# Moty_Light.net
KiCad netlist of a schematic drawn in EAGLE
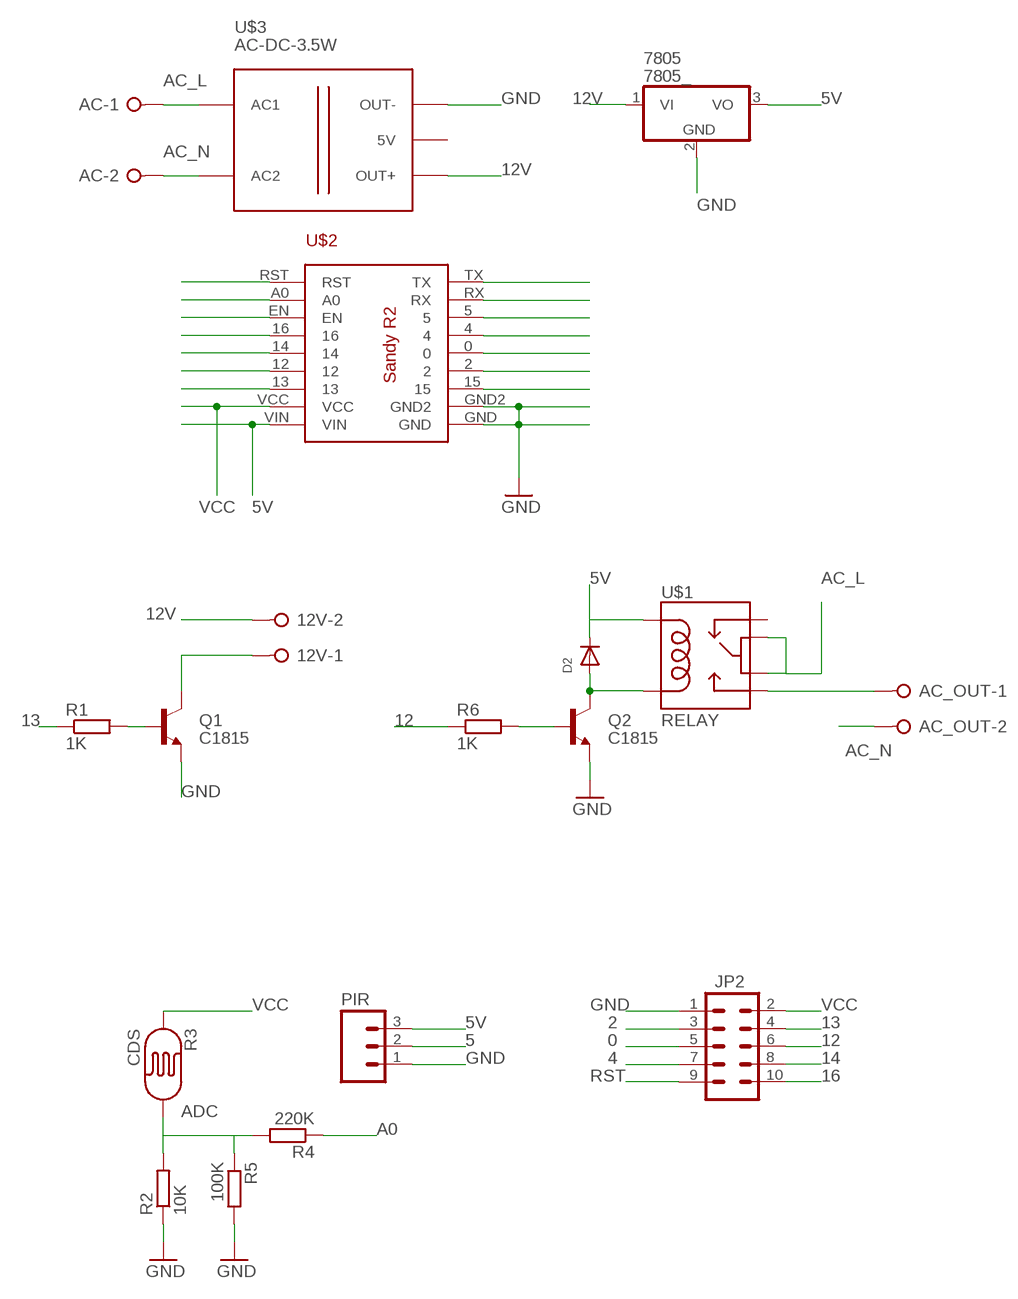
[diagram p0: schematic, sheet 1]

(export (version "E")
  (design (tool "Eeschema 10.0.6"))
  (components
    (comp (ref "12V")
      (value "W237-02P")
      (footprint "eagle-import:W237-132")
      (libsource (lib "eagle-import") (part "W237-02P"))
    )
    (comp (ref "7805")
      (value "7805_")
      (footprint "eagle-import:TO220V")
      (libsource (lib "eagle-import") (part "78TV05"))
    )
    (comp (ref "AC")
      (value "W237-02P")
      (footprint "eagle-import:W237-132")
      (libsource (lib "eagle-import") (part "W237-02P"))
    )
    (comp (ref "AC_OUT")
      (value "W237-02P")
      (footprint "eagle-import:W237-132")
      (libsource (lib "eagle-import") (part "W237-02P"))
    )
    (comp (ref "D2")
      (value "DIODESMA")
      (footprint "eagle-import:SMADIODE")
      (libsource (lib "eagle-import") (part "DIODESMA"))
    )
    (comp (ref "JP2")
      (value "M05X2PTH")
      (footprint "eagle-import:AVR_ICSP")
      (libsource (lib "eagle-import") (part "M05X2PTH"))
    )
    (comp (ref "PIR")
      (value "M03PTH")
      (footprint "eagle-import:1X03")
      (libsource (lib "eagle-import") (part "M03PTH"))
    )
    (comp (ref "Q1")
      (value "C1815")
      (footprint "eagle-import:SOT23-3")
      (libsource (lib "eagle-import") (part "TRANSISTOR_NPNMMBT2222A"))
    )
    (comp (ref "Q2")
      (value "C1815")
      (footprint "eagle-import:SOT23-3")
      (libsource (lib "eagle-import") (part "TRANSISTOR_NPNMMBT2222A"))
    )
    (comp (ref "R1")
      (value "1K")
      (footprint "eagle-import:R0805")
      (libsource (lib "eagle-import") (part "R-EU_R0805"))
    )
    (comp (ref "R2")
      (value "10K")
      (footprint "eagle-import:R0805")
      (libsource (lib "eagle-import") (part "R-EU_R0805"))
    )
    (comp (ref "R3")
      (value "CDS")
      (footprint "eagle-import:PHOTOCELL_THIN")
      (libsource (lib "eagle-import") (part "PHOTOCELL"))
    )
    (comp (ref "R4")
      (value "220K")
      (footprint "eagle-import:R0805")
      (libsource (lib "eagle-import") (part "R-EU_R0805"))
    )
    (comp (ref "R5")
      (value "100K")
      (footprint "eagle-import:R0805")
      (libsource (lib "eagle-import") (part "R-EU_R0805"))
    )
    (comp (ref "R6")
      (value "1K")
      (footprint "eagle-import:R0805")
      (libsource (lib "eagle-import") (part "R-EU_R0805"))
    )
    (comp (ref "U$1")
      (value "RELAY")
      (footprint "eagle-import:MINIATURE_RELAY_JRC_21F")
      (libsource (lib "eagle-import") (part "MINIATURE_RELAY_JRC_21F"))
    )
    (comp (ref "U$2")
      (value "MINI-ESP")
      (footprint "eagle-import:MINI-ESP")
      (libsource (lib "eagle-import") (part "MINI-ESP"))
    )
    (comp (ref "U$3")
      (value "AC-DC-3.5W")
      (footprint "eagle-import:AC-DC-3.5W")
      (libsource (lib "eagle-import") (part "AC-DC-3.5W"))
    )
  )
  (nets
    (net (code "1") (name "/0") (class "Default")
      (node (ref "JP2") (pin "5") (pinfunction "5_5") (pintype "passive"))
      (node (ref "U$2") (pin "0") (pinfunction "0_0") (pintype "bidirectional"))
    )
    (net (code "2") (name "/2") (class "Default")
      (node (ref "JP2") (pin "3") (pinfunction "3_3") (pintype "passive"))
      (node (ref "U$2") (pin "2") (pinfunction "2_2") (pintype "bidirectional"))
    )
    (net (code "3") (name "/4") (class "Default")
      (node (ref "JP2") (pin "7") (pinfunction "7_7") (pintype "passive"))
      (node (ref "U$2") (pin "4") (pinfunction "4_4") (pintype "bidirectional"))
    )
    (net (code "4") (name "/5") (class "Default")
      (node (ref "PIR") (pin "2") (pinfunction "2_2") (pintype "passive"))
      (node (ref "U$2") (pin "5") (pinfunction "5_5") (pintype "bidirectional"))
    )
    (net (code "5") (name "/5V") (class "Default")
      (node (ref "7805") (pin "3") (pinfunction "VO_3") (pintype "passive"))
      (node (ref "D2") (pin "C") (pinfunction "C_C") (pintype "passive"))
      (node (ref "PIR") (pin "3") (pinfunction "3_3") (pintype "passive"))
      (node (ref "U$1") (pin "COIL1") (pinfunction "COIL1_COIL1") (pintype "bidirectional"))
      (node (ref "U$2") (pin "VIN") (pinfunction "VIN_VIN") (pintype "bidirectional"))
    )
    (net (code "6") (name "/12") (class "Default")
      (node (ref "JP2") (pin "6") (pinfunction "6_6") (pintype "passive"))
      (node (ref "R6") (pin "1") (pinfunction "1_1") (pintype "passive"))
      (node (ref "U$2") (pin "12") (pinfunction "12_12") (pintype "bidirectional"))
    )
    (net (code "7") (name "/12V") (class "Default")
      (node (ref "12V") (pin "2") (pinfunction "KL_2") (pintype "passive"))
      (node (ref "7805") (pin "1") (pinfunction "VI_1") (pintype "input"))
      (node (ref "U$3") (pin "J2.3") (pinfunction "OUT+_J2.3") (pintype "bidirectional"))
    )
    (net (code "8") (name "/13") (class "Default")
      (node (ref "JP2") (pin "4") (pinfunction "4_4") (pintype "passive"))
      (node (ref "R1") (pin "1") (pinfunction "1_1") (pintype "passive"))
      (node (ref "U$2") (pin "13") (pinfunction "13_13") (pintype "bidirectional"))
    )
    (net (code "9") (name "/14") (class "Default")
      (node (ref "JP2") (pin "8") (pinfunction "8_8") (pintype "passive"))
      (node (ref "U$2") (pin "14") (pinfunction "14_14") (pintype "bidirectional"))
    )
    (net (code "10") (name "/16") (class "Default")
      (node (ref "JP2") (pin "10") (pinfunction "10_10") (pintype "passive"))
      (node (ref "U$2") (pin "16") (pinfunction "16_16") (pintype "bidirectional"))
    )
    (net (code "11") (name "/A0") (class "Default")
      (node (ref "R4") (pin "1") (pinfunction "1_1") (pintype "passive"))
      (node (ref "U$2") (pin "A0") (pinfunction "A0_A0") (pintype "bidirectional"))
    )
    (net (code "12") (name "/AC_L") (class "Default")
      (node (ref "AC") (pin "1") (pinfunction "KL_1") (pintype "passive"))
      (node (ref "U$1") (pin "COM1") (pinfunction "COM1_COM1") (pintype "bidirectional"))
      (node (ref "U$1") (pin "COM2") (pinfunction "COM2_COM2") (pintype "bidirectional"))
      (node (ref "U$3") (pin "J1.1") (pinfunction "AC1_J1.1") (pintype "bidirectional"))
    )
    (net (code "13") (name "/AC_N") (class "Default")
      (node (ref "AC") (pin "2") (pinfunction "KL_2") (pintype "passive"))
      (node (ref "AC_OUT") (pin "2") (pinfunction "KL_2") (pintype "passive"))
      (node (ref "U$3") (pin "J1.2") (pinfunction "AC2_J1.2") (pintype "bidirectional"))
    )
    (net (code "14") (name "/ADC") (class "Default")
      (node (ref "R2") (pin "2") (pinfunction "2_2") (pintype "passive"))
      (node (ref "R3") (pin "2") (pinfunction "P$2_2") (pintype "bidirectional"))
      (node (ref "R4") (pin "2") (pinfunction "2_2") (pintype "passive"))
      (node (ref "R5") (pin "1") (pinfunction "1_1") (pintype "passive"))
    )
    (net (code "15") (name "/RST") (class "Default")
      (node (ref "JP2") (pin "9") (pinfunction "9_9") (pintype "passive"))
      (node (ref "U$2") (pin "RST") (pinfunction "RST_RST") (pintype "bidirectional"))
    )
    (net (code "16") (name "/VCC") (class "Default")
      (node (ref "JP2") (pin "2") (pinfunction "2_2") (pintype "passive"))
      (node (ref "R3") (pin "1") (pinfunction "P$1_1") (pintype "bidirectional"))
      (node (ref "U$2") (pin "VCC") (pinfunction "VCC_VCC") (pintype "bidirectional"))
    )
    (net (code "17") (name "GND") (class "Default")
      (node (ref "7805") (pin "2") (pinfunction "GND_2") (pintype "passive"))
      (node (ref "JP2") (pin "1") (pinfunction "1_1") (pintype "passive"))
      (node (ref "PIR") (pin "1") (pinfunction "1_1") (pintype "passive"))
      (node (ref "Q1") (pin "2") (pinfunction "E_2") (pintype "passive"))
      (node (ref "Q2") (pin "2") (pinfunction "E_2") (pintype "passive"))
      (node (ref "R2") (pin "1") (pinfunction "1_1") (pintype "passive"))
      (node (ref "R5") (pin "2") (pinfunction "2_2") (pintype "passive"))
      (node (ref "U$2") (pin "GND") (pinfunction "GND_GND") (pintype "bidirectional"))
      (node (ref "U$2") (pin "GND2") (pinfunction "GND2_GND2") (pintype "bidirectional"))
      (node (ref "U$3") (pin "J2.1") (pinfunction "OUT-_J2.1") (pintype "bidirectional"))
    )
    (net (code "18") (name "Net-(12VA-KL)") (class "Default")
      (node (ref "12V") (pin "1") (pinfunction "KL_1") (pintype "passive"))
      (node (ref "Q1") (pin "3") (pinfunction "C_3") (pintype "passive"))
    )
    (net (code "19") (name "Net-(AC_OUTA-KL)") (class "Default")
      (node (ref "AC_OUT") (pin "1") (pinfunction "KL_1") (pintype "passive"))
      (node (ref "U$1") (pin "NO") (pinfunction "NO_NO") (pintype "bidirectional"))
    )
    (net (code "20") (name "Net-(Q1-B)") (class "Default")
      (node (ref "Q1") (pin "1") (pinfunction "B_1") (pintype "passive"))
      (node (ref "R1") (pin "2") (pinfunction "2_2") (pintype "passive"))
    )
    (net (code "21") (name "Net-(Q2-B)") (class "Default")
      (node (ref "Q2") (pin "1") (pinfunction "B_1") (pintype "passive"))
      (node (ref "R6") (pin "2") (pinfunction "2_2") (pintype "passive"))
    )
    (net (code "22") (name "Net-(Q2-C)") (class "Default")
      (node (ref "D2") (pin "A") (pinfunction "A_A") (pintype "passive"))
      (node (ref "Q2") (pin "3") (pinfunction "C_3") (pintype "passive"))
      (node (ref "U$1") (pin "COIL2") (pinfunction "COIL2_COIL2") (pintype "bidirectional"))
    )
    (net (code "23") (name "unconnected-(U$1-PadNC)") (class "Default")
      (node (ref "U$1") (pin "NC") (pinfunction "NC_NC") (pintype "bidirectional"))
    )
    (net (code "24") (name "unconnected-(U$2-Pad15)") (class "Default")
      (node (ref "U$2") (pin "15") (pinfunction "15_15") (pintype "bidirectional"))
    )
    (net (code "25") (name "unconnected-(U$2-PadEN)") (class "Default")
      (node (ref "U$2") (pin "EN") (pinfunction "EN_EN") (pintype "bidirectional"))
    )
    (net (code "26") (name "unconnected-(U$2-PadRX)") (class "Default")
      (node (ref "U$2") (pin "RX") (pinfunction "RX_RX") (pintype "bidirectional"))
    )
    (net (code "27") (name "unconnected-(U$2-PadTX)") (class "Default")
      (node (ref "U$2") (pin "TX") (pinfunction "TX_TX") (pintype "bidirectional"))
    )
    (net (code "28") (name "unconnected-(U$3-5V-PadJ2.2)") (class "Default")
      (node (ref "U$3") (pin "J2.2") (pinfunction "5V_J2.2") (pintype "bidirectional"))
    )
  )
)
